# hhv-dcdarknet-display.net
KiCad netlist of a schematic drawn in EAGLE
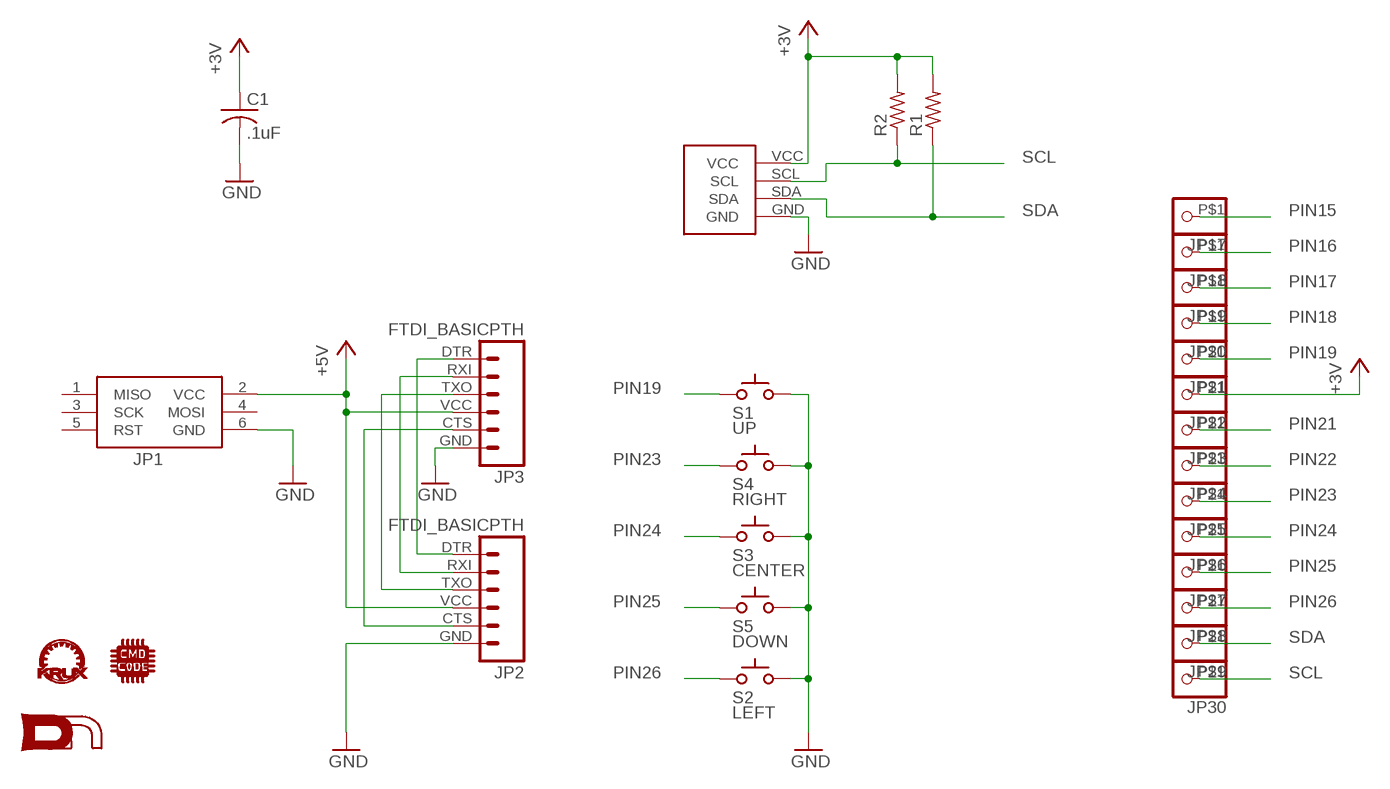
[diagram p0: schematic, sheet 1]

(export (version "E")
  (design (tool "Eeschema 10.0.6"))
  (components
    (comp (ref "C1")
      (value ".1uF")
      (footprint "eagle-import:C025-030X050")
      (libsource (lib "eagle-import") (part "C-US025-030X050"))
    )
    (comp (ref "JP1")
      (value "JP1")
      (footprint "eagle-import:AVRISP")
      (libsource (lib "eagle-import") (part "AVRISP-6"))
    )
    (comp (ref "JP2")
      (value "FTDI_BASICPTH")
      (footprint "eagle-import:FTDI_BASIC")
      (libsource (lib "eagle-import") (part "FTDI_BASICPTH"))
    )
    (comp (ref "JP3")
      (value "FTDI_BASICPTH")
      (footprint "eagle-import:FTDI_BASIC")
      (libsource (lib "eagle-import") (part "FTDI_BASICPTH"))
    )
    (comp (ref "JP17")
      (value "PINHD-1X11X1_SQUARE")
      (footprint "eagle-import:1X1-SMALL_CUT")
      (libsource (lib "eagle-import") (part "PINHD-1X11X1_SQUARE"))
    )
    (comp (ref "JP18")
      (value "PINHD-1X11X1_SQUARE")
      (footprint "eagle-import:1X1-SMALL_CUT")
      (libsource (lib "eagle-import") (part "PINHD-1X11X1_SQUARE"))
    )
    (comp (ref "JP19")
      (value "PINHD-1X11X1_SQUARE")
      (footprint "eagle-import:1X1-SMALL_CUT")
      (libsource (lib "eagle-import") (part "PINHD-1X11X1_SQUARE"))
    )
    (comp (ref "JP20")
      (value "PINHD-1X11X1_SQUARE")
      (footprint "eagle-import:1X1-SMALL_CUT")
      (libsource (lib "eagle-import") (part "PINHD-1X11X1_SQUARE"))
    )
    (comp (ref "JP21")
      (value "PINHD-1X11X1_SQUARE")
      (footprint "eagle-import:1X1-SMALL_CUT")
      (libsource (lib "eagle-import") (part "PINHD-1X11X1_SQUARE"))
    )
    (comp (ref "JP22")
      (value "PINHD-1X11X1_SQUARE")
      (footprint "eagle-import:1X1-SMALL_CUT")
      (libsource (lib "eagle-import") (part "PINHD-1X11X1_SQUARE"))
    )
    (comp (ref "JP23")
      (value "PINHD-1X11X1_SQUARE")
      (footprint "eagle-import:1X1-SMALL_CUT")
      (libsource (lib "eagle-import") (part "PINHD-1X11X1_SQUARE"))
    )
    (comp (ref "JP24")
      (value "PINHD-1X11X1_SQUARE")
      (footprint "eagle-import:1X1-SMALL_CUT")
      (libsource (lib "eagle-import") (part "PINHD-1X11X1_SQUARE"))
    )
    (comp (ref "JP25")
      (value "PINHD-1X11X1_SQUARE")
      (footprint "eagle-import:1X1-SMALL_CUT")
      (libsource (lib "eagle-import") (part "PINHD-1X11X1_SQUARE"))
    )
    (comp (ref "JP26")
      (value "PINHD-1X11X1_SQUARE")
      (footprint "eagle-import:1X1-SMALL_CUT")
      (libsource (lib "eagle-import") (part "PINHD-1X11X1_SQUARE"))
    )
    (comp (ref "JP27")
      (value "PINHD-1X11X1_SQUARE")
      (footprint "eagle-import:1X1-SMALL_CUT")
      (libsource (lib "eagle-import") (part "PINHD-1X11X1_SQUARE"))
    )
    (comp (ref "JP28")
      (value "PINHD-1X11X1_SQUARE")
      (footprint "eagle-import:1X1-SMALL_CUT")
      (libsource (lib "eagle-import") (part "PINHD-1X11X1_SQUARE"))
    )
    (comp (ref "JP29")
      (value "PINHD-1X11X1_SQUARE")
      (footprint "eagle-import:1X1-SMALL_CUT")
      (libsource (lib "eagle-import") (part "PINHD-1X11X1_SQUARE"))
    )
    (comp (ref "JP30")
      (value "PINHD-1X11X1_SQUARE")
      (footprint "eagle-import:1X1-SMALL_CUT")
      (libsource (lib "eagle-import") (part "PINHD-1X11X1_SQUARE"))
    )
    (comp (ref "R1")
      (value "R-US_0204/7")
      (footprint "eagle-import:0204_7")
      (libsource (lib "eagle-import") (part "R-US_0204/7"))
    )
    (comp (ref "R2")
      (value "R-US_0204/7")
      (footprint "eagle-import:0204_7")
      (libsource (lib "eagle-import") (part "R-US_0204/7"))
    )
    (comp (ref "S1")
      (value "UP")
      (footprint "eagle-import:TACTILE-2PIN")
      (libsource (lib "eagle-import") (part "SWITCH_TACTILETACTILE-2PIN"))
    )
    (comp (ref "S2")
      (value "LEFT")
      (footprint "eagle-import:TACTILE-2PIN")
      (libsource (lib "eagle-import") (part "SWITCH_TACTILETACTILE-2PIN"))
    )
    (comp (ref "S3")
      (value "CENTER")
      (footprint "eagle-import:TACTILE-2PIN")
      (libsource (lib "eagle-import") (part "SWITCH_TACTILETACTILE-2PIN"))
    )
    (comp (ref "S4")
      (value "RIGHT")
      (footprint "eagle-import:TACTILE-2PIN")
      (libsource (lib "eagle-import") (part "SWITCH_TACTILETACTILE-2PIN"))
    )
    (comp (ref "S5")
      (value "DOWN")
      (footprint "eagle-import:TACTILE-2PIN")
      (libsource (lib "eagle-import") (part "SWITCH_TACTILETACTILE-2PIN"))
    )
    (comp (ref "U$1")
      (value "KRUX_LOGO")
      (footprint "eagle-import:KRUX_LOGO")
      (libsource (lib "eagle-import") (part "KRUX_LOGO"))
    )
    (comp (ref "U$2")
      (value "DN_LOGO")
      (footprint "eagle-import:DN_LOGO")
      (libsource (lib "eagle-import") (part "DN_LOGO"))
    )
    (comp (ref "U$3")
      (value "I2C_0.96_OLEDOLED")
      (footprint "eagle-import:I2C_0.96_OLED")
      (libsource (lib "eagle-import") (part "I2C_0.96_OLEDOLED"))
    )
    (comp (ref "U$4")
      (value "CMDC0DE_LOGO")
      (footprint "eagle-import:CMDC0DE")
      (libsource (lib "eagle-import") (part "CMDC0DE_LOGO"))
    )
  )
  (nets
    (net (code "1") (name "+3V") (class "Default")
      (node (ref "C1") (pin "1") (pinfunction "1_1") (pintype "passive"))
      (node (ref "JP22") (pin "P$1") (pinfunction "1_P$1") (pintype "passive"))
      (node (ref "R1") (pin "2") (pinfunction "2_2") (pintype "passive"))
      (node (ref "R2") (pin "2") (pinfunction "2_2") (pintype "passive"))
      (node (ref "U$3") (pin "VCC") (pinfunction "VCC_VCC") (pintype "bidirectional"))
    )
    (net (code "2") (name "+5V") (class "Default")
      (node (ref "JP1") (pin "2") (pinfunction "VCC_2") (pintype "power_in"))
      (node (ref "JP2") (pin "VCC") (pinfunction "4_VCC") (pintype "passive"))
      (node (ref "JP3") (pin "VCC") (pinfunction "4_VCC") (pintype "passive"))
    )
    (net (code "3") (name "/PIN19") (class "Default")
      (node (ref "JP21") (pin "P$1") (pinfunction "1_P$1") (pintype "passive"))
      (node (ref "S1") (pin "P$2") (pinfunction "C_P$2") (pintype "passive"))
    )
    (net (code "4") (name "/PIN23") (class "Default")
      (node (ref "JP25") (pin "P$1") (pinfunction "1_P$1") (pintype "passive"))
      (node (ref "S4") (pin "P$2") (pinfunction "C_P$2") (pintype "passive"))
    )
    (net (code "5") (name "/PIN24") (class "Default")
      (node (ref "JP26") (pin "P$1") (pinfunction "1_P$1") (pintype "passive"))
      (node (ref "S3") (pin "P$2") (pinfunction "C_P$2") (pintype "passive"))
    )
    (net (code "6") (name "/PIN25") (class "Default")
      (node (ref "JP27") (pin "P$1") (pinfunction "1_P$1") (pintype "passive"))
      (node (ref "S5") (pin "P$2") (pinfunction "C_P$2") (pintype "passive"))
    )
    (net (code "7") (name "/PIN26") (class "Default")
      (node (ref "JP28") (pin "P$1") (pinfunction "1_P$1") (pintype "passive"))
      (node (ref "S2") (pin "P$2") (pinfunction "C_P$2") (pintype "passive"))
    )
    (net (code "8") (name "/PIN27") (class "Default")
      (node (ref "JP29") (pin "P$1") (pinfunction "1_P$1") (pintype "passive"))
      (node (ref "R1") (pin "1") (pinfunction "1_1") (pintype "passive"))
      (node (ref "U$3") (pin "SDA") (pinfunction "SDA_SDA") (pintype "bidirectional"))
    )
    (net (code "9") (name "/PIN28") (class "Default")
      (node (ref "JP30") (pin "P$1") (pinfunction "1_P$1") (pintype "passive"))
      (node (ref "R2") (pin "1") (pinfunction "1_1") (pintype "passive"))
      (node (ref "U$3") (pin "SCL") (pinfunction "SCL_SCL") (pintype "bidirectional"))
    )
    (net (code "10") (name "GND") (class "Default")
      (node (ref "C1") (pin "2") (pinfunction "2_2") (pintype "passive"))
      (node (ref "JP1") (pin "6") (pinfunction "GND_6") (pintype "power_in"))
      (node (ref "JP2") (pin "GND") (pinfunction "6_GND") (pintype "passive"))
      (node (ref "JP3") (pin "GND") (pinfunction "6_GND") (pintype "passive"))
      (node (ref "S1") (pin "P$1") (pinfunction "A_P$1") (pintype "passive"))
      (node (ref "S2") (pin "P$1") (pinfunction "A_P$1") (pintype "passive"))
      (node (ref "S3") (pin "P$1") (pinfunction "A_P$1") (pintype "passive"))
      (node (ref "S4") (pin "P$1") (pinfunction "A_P$1") (pintype "passive"))
      (node (ref "S5") (pin "P$1") (pinfunction "A_P$1") (pintype "passive"))
      (node (ref "U$3") (pin "GND") (pinfunction "GND_GND") (pintype "bidirectional"))
    )
    (net (code "11") (name "Net-(JP2-1)") (class "Default")
      (node (ref "JP2") (pin "DTR") (pinfunction "1_DTR") (pintype "passive"))
      (node (ref "JP3") (pin "DTR") (pinfunction "1_DTR") (pintype "passive"))
    )
    (net (code "12") (name "Net-(JP2-2)") (class "Default")
      (node (ref "JP2") (pin "RXI") (pinfunction "2_RXI") (pintype "passive"))
      (node (ref "JP3") (pin "RXI") (pinfunction "2_RXI") (pintype "passive"))
    )
    (net (code "13") (name "Net-(JP2-3)") (class "Default")
      (node (ref "JP2") (pin "TXO") (pinfunction "3_TXO") (pintype "passive"))
      (node (ref "JP3") (pin "TXO") (pinfunction "3_TXO") (pintype "passive"))
    )
    (net (code "14") (name "Net-(JP2-5)") (class "Default")
      (node (ref "JP2") (pin "CTS") (pinfunction "5_CTS") (pintype "passive"))
      (node (ref "JP3") (pin "CTS") (pinfunction "5_CTS") (pintype "passive"))
    )
    (net (code "15") (name "unconnected-(JP1-MISO-Pad1)") (class "Default")
      (node (ref "JP1") (pin "1") (pinfunction "MISO_1") (pintype "input"))
    )
    (net (code "16") (name "unconnected-(JP1-MOSI-Pad4)") (class "Default")
      (node (ref "JP1") (pin "4") (pinfunction "MOSI_4") (pintype "output"))
    )
    (net (code "17") (name "unconnected-(JP1-RST-Pad5)") (class "Default")
      (node (ref "JP1") (pin "5") (pinfunction "RST_5") (pintype "output"))
    )
    (net (code "18") (name "unconnected-(JP1-SCK-Pad3)") (class "Default")
      (node (ref "JP1") (pin "3") (pinfunction "SCK_3") (pintype "output"))
    )
    (net (code "19") (name "unconnected-(JP17-1-PadP$1)") (class "Default")
      (node (ref "JP17") (pin "P$1") (pinfunction "1_P$1") (pintype "passive"))
    )
    (net (code "20") (name "unconnected-(JP18-1-PadP$1)") (class "Default")
      (node (ref "JP18") (pin "P$1") (pinfunction "1_P$1") (pintype "passive"))
    )
    (net (code "21") (name "unconnected-(JP19-1-PadP$1)") (class "Default")
      (node (ref "JP19") (pin "P$1") (pinfunction "1_P$1") (pintype "passive"))
    )
    (net (code "22") (name "unconnected-(JP20-1-PadP$1)") (class "Default")
      (node (ref "JP20") (pin "P$1") (pinfunction "1_P$1") (pintype "passive"))
    )
    (net (code "23") (name "unconnected-(JP23-1-PadP$1)") (class "Default")
      (node (ref "JP23") (pin "P$1") (pinfunction "1_P$1") (pintype "passive"))
    )
    (net (code "24") (name "unconnected-(JP24-1-PadP$1)") (class "Default")
      (node (ref "JP24") (pin "P$1") (pinfunction "1_P$1") (pintype "passive"))
    )
  )
)
